# Raspberry_Pi.net
KiCad netlist of a schematic drawn in Altium Designer
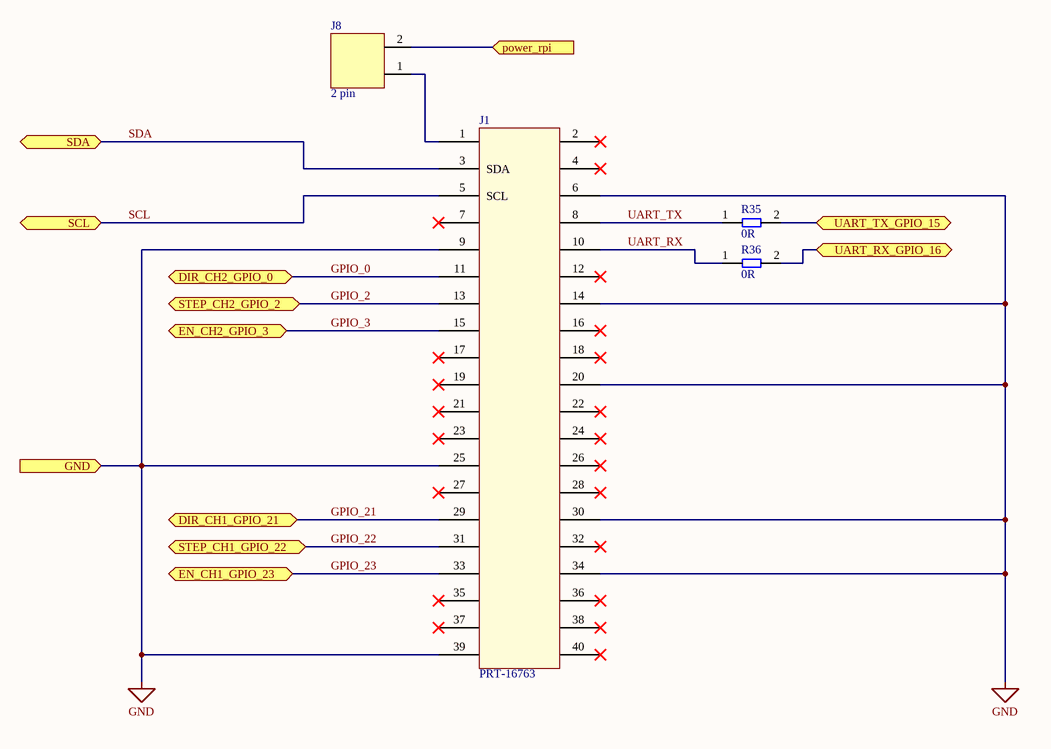
[diagram p0: Raspberry Pi.SchDoc]

(export (version "E")
  (design (tool "Eeschema 10.0.6"))
  (components
    (comp (ref "J1")
      (value "PRT-16763")
      (footprint "FP-SFH11-PBPC-D20-ST-BK-MFG")
      (description "Headers & Wire Housings Extended GPIO Female Header - 2x20 Pin (16mm/7.30mm)")
      (libsource (lib "Callisto Control Board") (part "Raspberry Pi 3+ Header"))
    )
    (comp (ref "J8")
      (value "2 pin")
      (footprint "2 pin header")
      (libsource (lib "Callisto Control Board") (part "2 pin male header 0.254mm"))
    )
    (comp (ref "R35")
      (value "0R")
      (footprint "0805 Resistor - IPC A")
      (description "Thick Film Resistors - SMD 0 Ohms 125 mW 0805 5%\r\nRC0805JR-070RL")
      (libsource (lib "Callisto Control Board") (part "RC0805JR-070RL"))
    )
    (comp (ref "R36")
      (value "0R")
      (footprint "0805 Resistor - IPC A")
      (description "Thick Film Resistors - SMD 0 Ohms 125 mW 0805 5%\r\nRC0805JR-070RL")
      (libsource (lib "Callisto Control Board") (part "RC0805JR-070RL"))
    )
  )
  (nets
    (net (code "1") (name "/GPIO_0") (class "Default")
      (node (ref "J1") (pin "11") (pinfunction "11_11") (pintype "passive"))
    )
    (net (code "2") (name "/GPIO_2") (class "Default")
      (node (ref "J1") (pin "13") (pinfunction "13_13") (pintype "passive"))
    )
    (net (code "3") (name "/GPIO_3") (class "Default")
      (node (ref "J1") (pin "15") (pinfunction "15_15") (pintype "passive"))
    )
    (net (code "4") (name "/GPIO_21") (class "Default")
      (node (ref "J1") (pin "29") (pinfunction "29_29") (pintype "passive"))
    )
    (net (code "5") (name "/GPIO_22") (class "Default")
      (node (ref "J1") (pin "31") (pinfunction "31_31") (pintype "passive"))
    )
    (net (code "6") (name "/GPIO_23") (class "Default")
      (node (ref "J1") (pin "33") (pinfunction "33_33") (pintype "passive"))
    )
    (net (code "7") (name "/SCL") (class "Default")
      (node (ref "J1") (pin "5") (pinfunction "SCL_5") (pintype "passive"))
    )
    (net (code "8") (name "/SDA") (class "Default")
      (node (ref "J1") (pin "3") (pinfunction "SDA_3") (pintype "passive"))
    )
    (net (code "9") (name "/UART_RX") (class "Default")
      (node (ref "J1") (pin "10") (pinfunction "10_10") (pintype "passive"))
      (node (ref "R36") (pin "1") (pintype "passive"))
    )
    (net (code "10") (name "/UART_RX_GPIO_16") (class "Default")
      (node (ref "R36") (pin "2") (pintype "passive"))
    )
    (net (code "11") (name "/UART_TX") (class "Default")
      (node (ref "J1") (pin "8") (pinfunction "8_8") (pintype "passive"))
      (node (ref "R35") (pin "1") (pintype "passive"))
    )
    (net (code "12") (name "/UART_TX_GPIO_15") (class "Default")
      (node (ref "R35") (pin "2") (pintype "passive"))
    )
    (net (code "13") (name "/power_rpi") (class "Default") (node (ref "J8") (pin "2") (pintype "passive")))
    (net (code "14") (name "GND") (class "Default")
      (node (ref "J1") (pin "14") (pinfunction "14_14") (pintype "passive"))
      (node (ref "J1") (pin "20") (pinfunction "20_20") (pintype "passive"))
      (node (ref "J1") (pin "25") (pinfunction "25_25") (pintype "passive"))
      (node (ref "J1") (pin "30") (pinfunction "30_30") (pintype "passive"))
      (node (ref "J1") (pin "34") (pinfunction "34_34") (pintype "passive"))
      (node (ref "J1") (pin "39") (pinfunction "39_39") (pintype "passive"))
      (node (ref "J1") (pin "6") (pinfunction "6_6") (pintype "passive"))
      (node (ref "J1") (pin "9") (pinfunction "9_9") (pintype "passive"))
    )
    (net (code "15") (name "Net-(J1-Pad1)") (class "Default")
      (node (ref "J1") (pin "1") (pintype "passive"))
      (node (ref "J8") (pin "1") (pintype "passive"))
    )
    (net (code "16") (name "unconnected-(J1-Pad2)") (class "Default")
      (node (ref "J1") (pin "2") (pintype "passive+no_connect"))
    )
    (net (code "17") (name "unconnected-(J1-Pad4)") (class "Default")
      (node (ref "J1") (pin "4") (pintype "passive+no_connect"))
    )
    (net (code "18") (name "unconnected-(J1-Pad7)") (class "Default")
      (node (ref "J1") (pin "7") (pinfunction "7_7") (pintype "passive+no_connect"))
    )
    (net (code "19") (name "unconnected-(J1-Pad12)") (class "Default")
      (node (ref "J1") (pin "12") (pinfunction "12_12") (pintype "passive+no_connect"))
    )
    (net (code "20") (name "unconnected-(J1-Pad16)") (class "Default")
      (node (ref "J1") (pin "16") (pinfunction "16_16") (pintype "passive+no_connect"))
    )
    (net (code "21") (name "unconnected-(J1-Pad17)") (class "Default")
      (node (ref "J1") (pin "17") (pinfunction "17_17") (pintype "passive+no_connect"))
    )
    (net (code "22") (name "unconnected-(J1-Pad18)") (class "Default")
      (node (ref "J1") (pin "18") (pinfunction "18_18") (pintype "passive+no_connect"))
    )
    (net (code "23") (name "unconnected-(J1-Pad19)") (class "Default")
      (node (ref "J1") (pin "19") (pinfunction "19_19") (pintype "passive+no_connect"))
    )
    (net (code "24") (name "unconnected-(J1-Pad21)") (class "Default")
      (node (ref "J1") (pin "21") (pinfunction "21_21") (pintype "passive+no_connect"))
    )
    (net (code "25") (name "unconnected-(J1-Pad22)") (class "Default")
      (node (ref "J1") (pin "22") (pinfunction "22_22") (pintype "passive+no_connect"))
    )
    (net (code "26") (name "unconnected-(J1-Pad23)") (class "Default")
      (node (ref "J1") (pin "23") (pinfunction "23_23") (pintype "passive+no_connect"))
    )
    (net (code "27") (name "unconnected-(J1-Pad24)") (class "Default")
      (node (ref "J1") (pin "24") (pinfunction "24_24") (pintype "passive+no_connect"))
    )
    (net (code "28") (name "unconnected-(J1-Pad26)") (class "Default")
      (node (ref "J1") (pin "26") (pinfunction "26_26") (pintype "passive+no_connect"))
    )
    (net (code "29") (name "unconnected-(J1-Pad27)") (class "Default")
      (node (ref "J1") (pin "27") (pinfunction "27_27") (pintype "passive+no_connect"))
    )
    (net (code "30") (name "unconnected-(J1-Pad28)") (class "Default")
      (node (ref "J1") (pin "28") (pinfunction "28_28") (pintype "passive+no_connect"))
    )
    (net (code "31") (name "unconnected-(J1-Pad32)") (class "Default")
      (node (ref "J1") (pin "32") (pinfunction "32_32") (pintype "passive+no_connect"))
    )
    (net (code "32") (name "unconnected-(J1-Pad35)") (class "Default")
      (node (ref "J1") (pin "35") (pinfunction "35_35") (pintype "passive+no_connect"))
    )
    (net (code "33") (name "unconnected-(J1-Pad36)") (class "Default")
      (node (ref "J1") (pin "36") (pinfunction "36_36") (pintype "passive+no_connect"))
    )
    (net (code "34") (name "unconnected-(J1-Pad37)") (class "Default")
      (node (ref "J1") (pin "37") (pinfunction "37_37") (pintype "passive+no_connect"))
    )
    (net (code "35") (name "unconnected-(J1-Pad38)") (class "Default")
      (node (ref "J1") (pin "38") (pinfunction "38_38") (pintype "passive+no_connect"))
    )
    (net (code "36") (name "unconnected-(J1-Pad40)") (class "Default")
      (node (ref "J1") (pin "40") (pinfunction "40_40") (pintype "passive+no_connect"))
    )
  )
)
